# DroneSch.net
KiCad netlist of a schematic drawn in Altium Designer
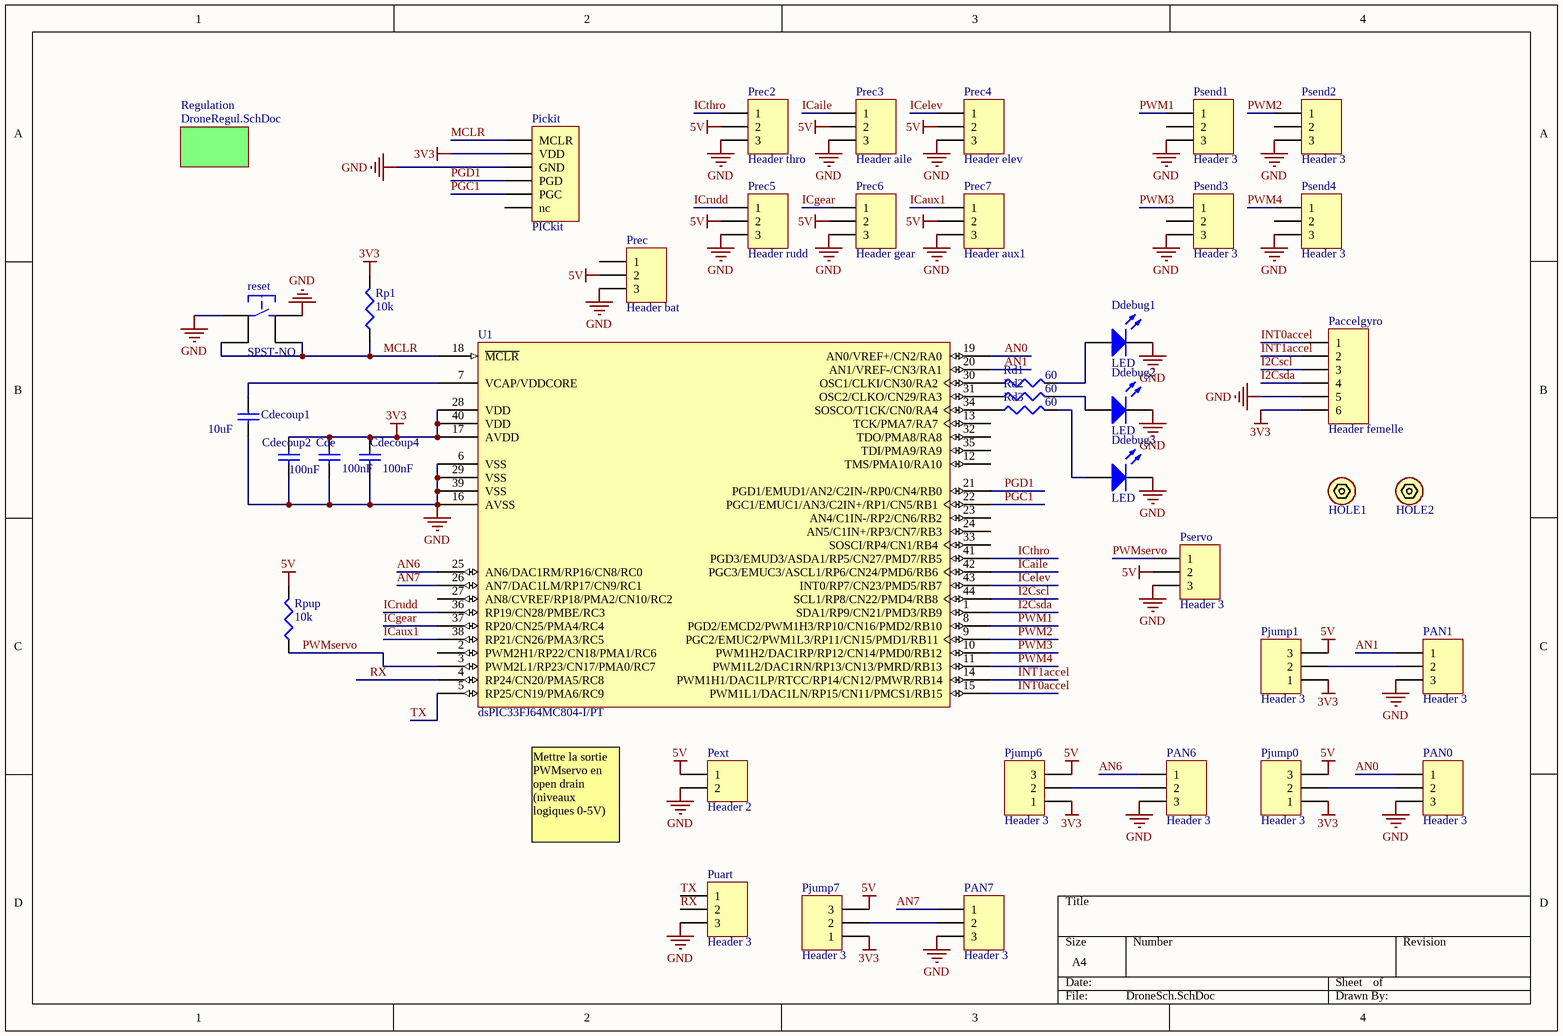
[diagram p0: DroneSch.SchDoc]

(export (version "E")
  (design (tool "Eeschema 10.0.6"))
  (components
    (comp (ref "Cde")
      (value "100nF")
      (footprint "C0805C")
      (description "Capacitor")
      (fields (field (name "Comment") "CAP") (field (name "PUBLISHER") "Altium Limited"))
      (libsource (lib "7Robot") (part "CAP"))
    )
    (comp (ref "Cdecoup1")
      (value "10uF")
      (footprint "C0805C")
      (description "Capacitor")
      (fields (field (name "Comment") "CAP") (field (name "PUBLISHER") "Altium Limited"))
      (libsource (lib "7Robot") (part "CAP"))
    )
    (comp (ref "Cdecoup2")
      (value "100nF")
      (footprint "C0805C")
      (description "Capacitor")
      (fields (field (name "Comment") "CAP") (field (name "PUBLISHER") "Altium Limited"))
      (libsource (lib "7Robot") (part "CAP"))
    )
    (comp (ref "Cdecoup4")
      (value "100nF")
      (footprint "C0805C")
      (description "Capacitor")
      (fields (field (name "Comment") "CAP") (field (name "PUBLISHER") "Altium Limited"))
      (libsource (lib "7Robot") (part "CAP"))
    )
    (comp (ref "Ddebug1")
      (value "LED")
      (footprint "LED1206R")
      (description "Typical LED")
      (fields (field (name "PUBLISHER") "Altium Limited"))
      (libsource (lib "7Robot") (part "LED"))
    )
    (comp (ref "Ddebug2")
      (value "LED")
      (footprint "LED1206Y")
      (description "Typical LED")
      (fields (field (name "PUBLISHER") "Altium Limited"))
      (libsource (lib "7Robot") (part "LED"))
    )
    (comp (ref "Ddebug3")
      (value "LED")
      (footprint "LED1206G")
      (description "Typical LED")
      (fields (field (name "PUBLISHER") "Altium Limited"))
      (libsource (lib "7Robot") (part "LED"))
    )
    (comp (ref "HOLE1")
      (value "Hole")
      (footprint "SCREW")
      (description "Mounting Hole for screws")
      (libsource (lib "7Robot") (part "Hole"))
    )
    (comp (ref "HOLE2")
      (value "Hole")
      (footprint "SCREW")
      (description "Mounting Hole for screws")
      (libsource (lib "7Robot") (part "Hole"))
    )
    (comp (ref "Paccelgyro")
      (value "Header femelle")
      (footprint "HDR1X6")
      (description "Header, 6-Pin")
      (fields (field (name "PUBLISHER") "Altium Limited"))
      (libsource (lib "7Robot") (part "Header 6"))
    )
    (comp (ref "PAN0")
      (value "Header 3")
      (footprint "HDR1X3")
      (description "Header, 3-Pin")
      (fields (field (name "PUBLISHER") "Altium Limited"))
      (libsource (lib "7Robot") (part "Header 3"))
    )
    (comp (ref "PAN1")
      (value "Header 3")
      (footprint "HDR1X3")
      (description "Header, 3-Pin")
      (fields (field (name "PUBLISHER") "Altium Limited"))
      (libsource (lib "7Robot") (part "Header 3"))
    )
    (comp (ref "PAN6")
      (value "Header 3")
      (footprint "HDR1X3")
      (description "Header, 3-Pin")
      (fields (field (name "PUBLISHER") "Altium Limited"))
      (libsource (lib "7Robot") (part "Header 3"))
    )
    (comp (ref "PAN7")
      (value "Header 3")
      (footprint "HDR1X3")
      (description "Header, 3-Pin")
      (fields (field (name "PUBLISHER") "Altium Limited"))
      (libsource (lib "7Robot") (part "Header 3"))
    )
    (comp (ref "Pext")
      (value "Header 2")
      (footprint "TERM2W-3.5")
      (description "Header, 2-Pin")
      (fields (field (name "PUBLISHER") "Altium Limited"))
      (libsource (lib "7Robot") (part "Header 2"))
    )
    (comp (ref "Pickit")
      (value "PICkit")
      (footprint "HDR1X6H")
      (description "Header, 6-Pin, Right Angle")
      (fields (field (name "PUBLISHER") "Altium Limited"))
      (libsource (lib "7Robot") (part "Header ICSP"))
    )
    (comp (ref "Pjump0")
      (value "Header 3")
      (footprint "HDR1X3")
      (description "Header, 3-Pin")
      (fields (field (name "PUBLISHER") "Altium Limited"))
      (libsource (lib "") (part "Header 3_1"))
    )
    (comp (ref "Pjump1")
      (value "Header 3")
      (footprint "HDR1X3")
      (description "Header, 3-Pin")
      (fields (field (name "PUBLISHER") "Altium Limited"))
      (libsource (lib "") (part "Header 3_1"))
    )
    (comp (ref "Pjump6")
      (value "Header 3")
      (footprint "HDR1X3")
      (description "Header, 3-Pin")
      (fields (field (name "PUBLISHER") "Altium Limited"))
      (libsource (lib "") (part "Header 3_1"))
    )
    (comp (ref "Pjump7")
      (value "Header 3")
      (footprint "HDR1X3")
      (description "Header, 3-Pin")
      (fields (field (name "PUBLISHER") "Altium Limited"))
      (libsource (lib "") (part "Header 3_1"))
    )
    (comp (ref "Prec")
      (value "Header bat")
      (footprint "HDR1X3")
      (description "Header, 3-Pin")
      (fields (field (name "PUBLISHER") "Altium Limited"))
      (libsource (lib "7Robot") (part "Header 3"))
    )
    (comp (ref "Prec2")
      (value "Header thro")
      (footprint "HDR1X3")
      (description "Header, 3-Pin")
      (fields (field (name "PUBLISHER") "Altium Limited"))
      (libsource (lib "7Robot") (part "Header 3"))
    )
    (comp (ref "Prec3")
      (value "Header aile")
      (footprint "HDR1X3")
      (description "Header, 3-Pin")
      (fields (field (name "PUBLISHER") "Altium Limited"))
      (libsource (lib "7Robot") (part "Header 3"))
    )
    (comp (ref "Prec4")
      (value "Header elev")
      (footprint "HDR1X3")
      (description "Header, 3-Pin")
      (fields (field (name "PUBLISHER") "Altium Limited"))
      (libsource (lib "7Robot") (part "Header 3"))
    )
    (comp (ref "Prec5")
      (value "Header rudd")
      (footprint "HDR1X3")
      (description "Header, 3-Pin")
      (fields (field (name "PUBLISHER") "Altium Limited"))
      (libsource (lib "7Robot") (part "Header 3"))
    )
    (comp (ref "Prec6")
      (value "Header gear")
      (footprint "HDR1X3")
      (description "Header, 3-Pin")
      (fields (field (name "PUBLISHER") "Altium Limited"))
      (libsource (lib "7Robot") (part "Header 3"))
    )
    (comp (ref "Prec7")
      (value "Header aux1")
      (footprint "HDR1X3")
      (description "Header, 3-Pin")
      (fields (field (name "PUBLISHER") "Altium Limited"))
      (libsource (lib "7Robot") (part "Header 3"))
    )
    (comp (ref "Psend1")
      (value "Header 3")
      (footprint "HDR1X3")
      (description "Header, 3-Pin")
      (fields (field (name "PUBLISHER") "Altium Limited"))
      (libsource (lib "7Robot") (part "Header 3"))
    )
    (comp (ref "Psend2")
      (value "Header 3")
      (footprint "HDR1X3")
      (description "Header, 3-Pin")
      (fields (field (name "PUBLISHER") "Altium Limited"))
      (libsource (lib "7Robot") (part "Header 3"))
    )
    (comp (ref "Psend3")
      (value "Header 3")
      (footprint "HDR1X3")
      (description "Header, 3-Pin")
      (fields (field (name "PUBLISHER") "Altium Limited"))
      (libsource (lib "7Robot") (part "Header 3"))
    )
    (comp (ref "Psend4")
      (value "Header 3")
      (footprint "HDR1X3")
      (description "Header, 3-Pin")
      (fields (field (name "PUBLISHER") "Altium Limited"))
      (libsource (lib "7Robot") (part "Header 3"))
    )
    (comp (ref "Pservo")
      (value "Header 3")
      (footprint "HDR1X3")
      (description "Header, 3-Pin")
      (fields (field (name "PUBLISHER") "Altium Limited"))
      (libsource (lib "7Robot") (part "Header 3"))
    )
    (comp (ref "Puart")
      (value "Header 3")
      (footprint "HDR1X3")
      (description "Header, 3-Pin")
      (fields (field (name "PUBLISHER") "Altium Limited"))
      (libsource (lib "7Robot") (part "Header 3"))
    )
    (comp (ref "Rd1")
      (value "60")
      (footprint "C0805R")
      (description "Resistor")
      (fields (field (name "Comment") "RES") (field (name "PUBLISHER") "Altium Limited"))
      (libsource (lib "7Robot") (part "RES"))
    )
    (comp (ref "Rd2")
      (value "60")
      (footprint "C0805R")
      (description "Resistor")
      (fields (field (name "Comment") "RES") (field (name "PUBLISHER") "Altium Limited"))
      (libsource (lib "7Robot") (part "RES"))
    )
    (comp (ref "Rd3")
      (value "60")
      (footprint "C0805R")
      (description "Resistor")
      (fields (field (name "Comment") "RES") (field (name "PUBLISHER") "Altium Limited"))
      (libsource (lib "7Robot") (part "RES"))
    )
    (comp (ref "reset")
      (value "SPST-NO")
      (footprint "SPST-NO")
      (description "Tactile Switch 7.3mm, SMD")
      (libsource (lib "7Robot") (part "SPST-NO"))
    )
    (comp (ref "Rp1")
      (value "10k")
      (footprint "C0805R")
      (description "Resistor")
      (fields (field (name "Comment") "RES") (field (name "PUBLISHER") "Altium Limited"))
      (libsource (lib "7Robot") (part "RES"))
    )
    (comp (ref "Rpup")
      (value "10k")
      (footprint "C0805R")
      (description "Resistor")
      (fields (field (name "Comment") "RES") (field (name "PUBLISHER") "Altium Limited"))
      (libsource (lib "7Robot") (part "RES"))
    )
    (comp (ref "U1")
      (value "dsPIC33FJ64MC804-I/PT")
      (footprint "TQFP-PT44_N")
      (fields (field (name "PUBLISHER") "Altium Limited"))
      (libsource (lib "7Robot") (part "dsPIC33FJ64MC804-I/PT"))
    )
  )
  (nets
    (net (code "1") (name "/AN0") (class "Default")
      (node (ref "PAN0") (pin "1") (pinfunction "1_1") (pintype "passive"))
      (node (ref "U1") (pin "19") (pinfunction "AN0/VREF+/CN2/RA0_19") (pintype "bidirectional"))
    )
    (net (code "2") (name "/AN1") (class "Default")
      (node (ref "PAN1") (pin "1") (pinfunction "1_1") (pintype "passive"))
      (node (ref "U1") (pin "20") (pinfunction "AN1/VREF-/CN3/RA1_20") (pintype "bidirectional"))
    )
    (net (code "3") (name "/AN6") (class "Default")
      (node (ref "PAN6") (pin "1") (pinfunction "1_1") (pintype "passive"))
      (node (ref "U1") (pin "25") (pinfunction "AN6/DAC1RM/RP16/CN8/RC0_25") (pintype "bidirectional"))
    )
    (net (code "4") (name "/AN7") (class "Default")
      (node (ref "PAN7") (pin "1") (pinfunction "1_1") (pintype "passive"))
      (node (ref "U1") (pin "26") (pinfunction "AN7/DAC1LM/RP17/CN9/RC1_26") (pintype "bidirectional"))
    )
    (net (code "5") (name "/I2Cscl") (class "Default")
      (node (ref "Paccelgyro") (pin "3") (pinfunction "3_3") (pintype "passive"))
      (node (ref "U1") (pin "44") (pinfunction "SCL1/RP8/CN22/PMD4/RB8_44") (pintype "bidirectional"))
    )
    (net (code "6") (name "/I2Csda") (class "Default")
      (node (ref "Paccelgyro") (pin "4") (pinfunction "4_4") (pintype "passive"))
      (node (ref "U1") (pin "1") (pinfunction "SDA1/RP9/CN21/PMD3/RB9_1") (pintype "bidirectional"))
    )
    (net (code "7") (name "/ICaile") (class "Default")
      (node (ref "Prec3") (pin "1") (pinfunction "1_1") (pintype "passive"))
      (node (ref "U1") (pin "42") (pinfunction "PGC3/EMUC3/ASCL1/RP6/CN24/PMD6/RB6_42") (pintype "bidirectional"))
    )
    (net (code "8") (name "/ICaux1") (class "Default")
      (node (ref "Prec7") (pin "1") (pinfunction "1_1") (pintype "passive"))
      (node (ref "U1") (pin "38") (pinfunction "RP21/CN26/PMA3/RC5_38") (pintype "bidirectional"))
    )
    (net (code "9") (name "/ICelev") (class "Default")
      (node (ref "Prec4") (pin "1") (pinfunction "1_1") (pintype "passive"))
      (node (ref "U1") (pin "43") (pinfunction "INT0/RP7/CN23/PMD5/RB7_43") (pintype "bidirectional"))
    )
    (net (code "10") (name "/ICgear") (class "Default")
      (node (ref "Prec6") (pin "1") (pinfunction "1_1") (pintype "passive"))
      (node (ref "U1") (pin "37") (pinfunction "RP20/CN25/PMA4/RC4_37") (pintype "bidirectional"))
    )
    (net (code "11") (name "/ICrudd") (class "Default")
      (node (ref "Prec5") (pin "1") (pinfunction "1_1") (pintype "passive"))
      (node (ref "U1") (pin "36") (pinfunction "RP19/CN28/PMBE/RC3_36") (pintype "bidirectional"))
    )
    (net (code "12") (name "/ICthro") (class "Default")
      (node (ref "Prec2") (pin "1") (pinfunction "1_1") (pintype "passive"))
      (node (ref "U1") (pin "41") (pinfunction "PGD3/EMUD3/ASDA1/RP5/CN27/PMD7/RB5_41") (pintype "bidirectional"))
    )
    (net (code "13") (name "/INT0accel") (class "Default")
      (node (ref "Paccelgyro") (pin "1") (pinfunction "1_1") (pintype "passive"))
      (node (ref "U1") (pin "15") (pinfunction "PWM1L1/DAC1LN/RP15/CN11/PMCS1/RB15_15") (pintype "bidirectional"))
    )
    (net (code "14") (name "/INT1accel") (class "Default")
      (node (ref "Paccelgyro") (pin "2") (pinfunction "2_2") (pintype "passive"))
      (node (ref "U1") (pin "14") (pinfunction "PWM1H1/DAC1LP/RTCC/RP14/CN12/PMWR/RB14_14") (pintype "bidirectional"))
    )
    (net (code "15") (name "/MCLR") (class "Default")
      (node (ref "Pickit") (pin "1") (pinfunction "MCLR_1") (pintype "passive"))
      (node (ref "Rp1") (pin "1") (pinfunction "1_1") (pintype "passive"))
      (node (ref "U1") (pin "18") (pinfunction "~{MCLR}_18") (pintype "input"))
      (node (ref "reset") (pin "2") (pintype "passive"))
      (node (ref "reset") (pin "3") (pintype "passive"))
    )
    (net (code "16") (name "/PGC1") (class "Default")
      (node (ref "Pickit") (pin "5") (pinfunction "PGC_5") (pintype "passive"))
      (node (ref "U1") (pin "22") (pinfunction "PGC1/EMUC1/AN3/C2IN+/RP1/CN5/RB1_22") (pintype "bidirectional"))
    )
    (net (code "17") (name "/PGD1") (class "Default")
      (node (ref "Pickit") (pin "4") (pinfunction "PGD_4") (pintype "passive"))
      (node (ref "U1") (pin "21") (pinfunction "PGD1/EMUD1/AN2/C2IN-/RP0/CN4/RB0_21") (pintype "bidirectional"))
    )
    (net (code "18") (name "/PWM1") (class "Default")
      (node (ref "Psend1") (pin "1") (pinfunction "1_1") (pintype "passive"))
      (node (ref "U1") (pin "8") (pinfunction "PGD2/EMCD2/PWM1H3/RP10/CN16/PMD2/RB10_8") (pintype "bidirectional"))
    )
    (net (code "19") (name "/PWM2") (class "Default")
      (node (ref "Psend2") (pin "1") (pinfunction "1_1") (pintype "passive"))
      (node (ref "U1") (pin "9") (pinfunction "PGC2/EMUC2/PWM1L3/RP11/CN15/PMD1/RB11_9") (pintype "bidirectional"))
    )
    (net (code "20") (name "/PWM3") (class "Default")
      (node (ref "Psend3") (pin "1") (pinfunction "1_1") (pintype "passive"))
      (node (ref "U1") (pin "10") (pinfunction "PWM1H2/DAC1RP/RP12/CN14/PMD0/RB12_10") (pintype "bidirectional"))
    )
    (net (code "21") (name "/PWM4") (class "Default")
      (node (ref "Psend4") (pin "1") (pinfunction "1_1") (pintype "passive"))
      (node (ref "U1") (pin "11") (pinfunction "PWM1L2/DAC1RN/RP13/CN13/PMRD/RB13_11") (pintype "bidirectional"))
    )
    (net (code "22") (name "/PWMservo") (class "Default")
      (node (ref "Pservo") (pin "1") (pinfunction "1_1") (pintype "passive"))
      (node (ref "Rpup") (pin "1") (pinfunction "1_1") (pintype "passive"))
      (node (ref "U1") (pin "3") (pinfunction "PWM2L1/RP23/CN17/PMA0/RC7_3") (pintype "bidirectional"))
    )
    (net (code "23") (name "/RX") (class "Default")
      (node (ref "Puart") (pin "2") (pinfunction "2_2") (pintype "passive"))
      (node (ref "U1") (pin "4") (pinfunction "RP24/CN20/PMA5/RC8_4") (pintype "bidirectional"))
    )
    (net (code "24") (name "/TX") (class "Default")
      (node (ref "Puart") (pin "1") (pinfunction "1_1") (pintype "passive"))
      (node (ref "U1") (pin "5") (pinfunction "RP25/CN19/PMA6/RC9_5") (pintype "bidirectional"))
    )
    (net (code "25") (name "3V3") (class "Default")
      (node (ref "Cde") (pin "2") (pinfunction "2_2") (pintype "passive"))
      (node (ref "Cdecoup2") (pin "2") (pinfunction "2_2") (pintype "passive"))
      (node (ref "Cdecoup4") (pin "2") (pinfunction "2_2") (pintype "passive"))
      (node (ref "Paccelgyro") (pin "6") (pinfunction "6_6") (pintype "passive"))
      (node (ref "Pickit") (pin "2") (pinfunction "VDD_2") (pintype "passive"))
      (node (ref "Pjump0") (pin "1") (pinfunction "1_1") (pintype "passive"))
      (node (ref "Pjump1") (pin "1") (pinfunction "1_1") (pintype "passive"))
      (node (ref "Pjump6") (pin "1") (pinfunction "1_1") (pintype "passive"))
      (node (ref "Pjump7") (pin "1") (pinfunction "1_1") (pintype "passive"))
      (node (ref "Rp1") (pin "2") (pinfunction "2_2") (pintype "passive"))
      (node (ref "U1") (pin "17") (pinfunction "AVDD_17") (pintype "power_in"))
      (node (ref "U1") (pin "28") (pinfunction "VDD_28") (pintype "power_in"))
      (node (ref "U1") (pin "40") (pinfunction "VDD_40") (pintype "power_in"))
    )
    (net (code "26") (name "5V") (class "Default")
      (node (ref "Pext") (pin "1") (pinfunction "1_1") (pintype "passive"))
      (node (ref "Pjump0") (pin "3") (pinfunction "3_3") (pintype "passive"))
      (node (ref "Pjump1") (pin "3") (pinfunction "3_3") (pintype "passive"))
      (node (ref "Pjump6") (pin "3") (pinfunction "3_3") (pintype "passive"))
      (node (ref "Pjump7") (pin "3") (pinfunction "3_3") (pintype "passive"))
      (node (ref "Prec") (pin "2") (pinfunction "2_2") (pintype "passive"))
      (node (ref "Prec2") (pin "2") (pinfunction "2_2") (pintype "passive"))
      (node (ref "Prec3") (pin "2") (pinfunction "2_2") (pintype "passive"))
      (node (ref "Prec4") (pin "2") (pinfunction "2_2") (pintype "passive"))
      (node (ref "Prec5") (pin "2") (pinfunction "2_2") (pintype "passive"))
      (node (ref "Prec6") (pin "2") (pinfunction "2_2") (pintype "passive"))
      (node (ref "Prec7") (pin "2") (pinfunction "2_2") (pintype "passive"))
      (node (ref "Pservo") (pin "2") (pinfunction "2_2") (pintype "passive"))
      (node (ref "Rpup") (pin "2") (pinfunction "2_2") (pintype "passive"))
    )
    (net (code "27") (name "GND") (class "Default")
      (node (ref "Cde") (pin "1") (pinfunction "1_1") (pintype "passive"))
      (node (ref "Cdecoup1") (pin "1") (pinfunction "1_1") (pintype "passive"))
      (node (ref "Cdecoup2") (pin "1") (pinfunction "1_1") (pintype "passive"))
      (node (ref "Cdecoup4") (pin "1") (pinfunction "1_1") (pintype "passive"))
      (node (ref "Ddebug1") (pin "2") (pinfunction "K_2") (pintype "passive"))
      (node (ref "Ddebug2") (pin "2") (pinfunction "K_2") (pintype "passive"))
      (node (ref "Ddebug3") (pin "2") (pinfunction "K_2") (pintype "passive"))
      (node (ref "PAN0") (pin "3") (pinfunction "3_3") (pintype "passive"))
      (node (ref "PAN1") (pin "3") (pinfunction "3_3") (pintype "passive"))
      (node (ref "PAN6") (pin "3") (pinfunction "3_3") (pintype "passive"))
      (node (ref "PAN7") (pin "3") (pinfunction "3_3") (pintype "passive"))
      (node (ref "Paccelgyro") (pin "5") (pinfunction "5_5") (pintype "passive"))
      (node (ref "Pext") (pin "2") (pinfunction "2_2") (pintype "passive"))
      (node (ref "Pickit") (pin "3") (pinfunction "GND_3") (pintype "passive"))
      (node (ref "Prec") (pin "3") (pinfunction "3_3") (pintype "passive"))
      (node (ref "Prec2") (pin "3") (pinfunction "3_3") (pintype "passive"))
      (node (ref "Prec3") (pin "3") (pinfunction "3_3") (pintype "passive"))
      (node (ref "Prec4") (pin "3") (pinfunction "3_3") (pintype "passive"))
      (node (ref "Prec5") (pin "3") (pinfunction "3_3") (pintype "passive"))
      (node (ref "Prec6") (pin "3") (pinfunction "3_3") (pintype "passive"))
      (node (ref "Prec7") (pin "3") (pinfunction "3_3") (pintype "passive"))
      (node (ref "Psend1") (pin "3") (pinfunction "3_3") (pintype "passive"))
      (node (ref "Psend2") (pin "3") (pinfunction "3_3") (pintype "passive"))
      (node (ref "Psend3") (pin "3") (pinfunction "3_3") (pintype "passive"))
      (node (ref "Psend4") (pin "3") (pinfunction "3_3") (pintype "passive"))
      (node (ref "Pservo") (pin "3") (pinfunction "3_3") (pintype "passive"))
      (node (ref "Puart") (pin "3") (pinfunction "3_3") (pintype "passive"))
      (node (ref "U1") (pin "16") (pinfunction "AVSS_16") (pintype "power_in"))
      (node (ref "U1") (pin "29") (pinfunction "VSS_29") (pintype "power_in"))
      (node (ref "U1") (pin "39") (pinfunction "VSS_39") (pintype "power_in"))
      (node (ref "U1") (pin "6") (pinfunction "VSS_6") (pintype "power_in"))
      (node (ref "reset") (pin "1") (pintype "passive"))
      (node (ref "reset") (pin "4") (pintype "passive"))
    )
    (net (code "28") (name "Net-(Ddebug1-A)") (class "Default")
      (node (ref "Ddebug1") (pin "1") (pinfunction "A_1") (pintype "passive"))
      (node (ref "Rd1") (pin "2") (pinfunction "2_2") (pintype "passive"))
    )
    (net (code "29") (name "Net-(Ddebug2-A)") (class "Default")
      (node (ref "Ddebug2") (pin "1") (pinfunction "A_1") (pintype "passive"))
      (node (ref "Rd2") (pin "2") (pinfunction "2_2") (pintype "passive"))
    )
    (net (code "30") (name "Net-(Ddebug3-A)") (class "Default")
      (node (ref "Ddebug3") (pin "1") (pinfunction "A_1") (pintype "passive"))
      (node (ref "Rd3") (pin "2") (pinfunction "2_2") (pintype "passive"))
    )
    (net (code "31") (name "Net-(PAN0-Pad2)") (class "Default")
      (node (ref "PAN0") (pin "2") (pinfunction "2_2") (pintype "passive"))
      (node (ref "Pjump0") (pin "2") (pinfunction "2_2") (pintype "passive"))
    )
    (net (code "32") (name "Net-(PAN1-Pad2)") (class "Default")
      (node (ref "PAN1") (pin "2") (pinfunction "2_2") (pintype "passive"))
      (node (ref "Pjump1") (pin "2") (pinfunction "2_2") (pintype "passive"))
    )
    (net (code "33") (name "Net-(PAN6-Pad2)") (class "Default")
      (node (ref "PAN6") (pin "2") (pinfunction "2_2") (pintype "passive"))
      (node (ref "Pjump6") (pin "2") (pinfunction "2_2") (pintype "passive"))
    )
    (net (code "34") (name "Net-(PAN7-Pad2)") (class "Default")
      (node (ref "PAN7") (pin "2") (pinfunction "2_2") (pintype "passive"))
      (node (ref "Pjump7") (pin "2") (pinfunction "2_2") (pintype "passive"))
    )
    (net (code "35") (name "Net-(U1-OSC1{slash}CLKI{slash}CN30{slash}RA2)") (class "Default")
      (node (ref "Rd1") (pin "1") (pinfunction "1_1") (pintype "passive"))
      (node (ref "U1") (pin "30") (pinfunction "OSC1/CLKI/CN30/RA2_30") (pintype "bidirectional"))
    )
    (net (code "36") (name "Net-(U1-OSC2{slash}CLKO{slash}CN29{slash}RA3)") (class "Default")
      (node (ref "Rd2") (pin "1") (pinfunction "1_1") (pintype "passive"))
      (node (ref "U1") (pin "31") (pinfunction "OSC2/CLKO/CN29/RA3_31") (pintype "bidirectional"))
    )
    (net (code "37") (name "Net-(U1-SOSCO{slash}T1CK{slash}CN0{slash}RA4)") (class "Default")
      (node (ref "Rd3") (pin "1") (pinfunction "1_1") (pintype "passive"))
      (node (ref "U1") (pin "34") (pinfunction "SOSCO/T1CK/CN0/RA4_34") (pintype "bidirectional"))
    )
    (net (code "38") (name "Net-(U1-VCAP{slash}VDDCORE)") (class "Default")
      (node (ref "Cdecoup1") (pin "2") (pinfunction "2_2") (pintype "passive"))
      (node (ref "U1") (pin "7") (pinfunction "VCAP/VDDCORE_7") (pintype "power_in"))
    )
    (net (code "39") (name "unconnected-(HOLE1-Hole-Pad1)") (class "Default")
      (node (ref "HOLE1") (pin "1") (pinfunction "Hole_1") (pintype "passive"))
    )
    (net (code "40") (name "unconnected-(HOLE2-Hole-Pad1)") (class "Default")
      (node (ref "HOLE2") (pin "1") (pinfunction "Hole_1") (pintype "passive"))
    )
    (net (code "41") (name "unconnected-(Pickit-nc-Pad6)") (class "Default")
      (node (ref "Pickit") (pin "6") (pinfunction "nc_6") (pintype "passive"))
    )
    (net (code "42") (name "unconnected-(Prec-Pad1)") (class "Default")
      (node (ref "Prec") (pin "1") (pinfunction "1_1") (pintype "passive"))
    )
    (net (code "43") (name "unconnected-(Psend1-Pad2)") (class "Default")
      (node (ref "Psend1") (pin "2") (pinfunction "2_2") (pintype "passive"))
    )
    (net (code "44") (name "unconnected-(Psend2-Pad2)") (class "Default")
      (node (ref "Psend2") (pin "2") (pinfunction "2_2") (pintype "passive"))
    )
    (net (code "45") (name "unconnected-(Psend3-Pad2)") (class "Default")
      (node (ref "Psend3") (pin "2") (pinfunction "2_2") (pintype "passive"))
    )
    (net (code "46") (name "unconnected-(Psend4-Pad2)") (class "Default")
      (node (ref "Psend4") (pin "2") (pinfunction "2_2") (pintype "passive"))
    )
    (net (code "47") (name "unconnected-(U1-AN4{slash}C1IN-{slash}RP2{slash}CN6{slash}RB2-Pad23)") (class "Default")
      (node (ref "U1") (pin "23") (pinfunction "AN4/C1IN-/RP2/CN6/RB2_23") (pintype "bidirectional"))
    )
    (net (code "48") (name "unconnected-(U1-AN5{slash}C1IN+{slash}RP3{slash}CN7{slash}RB3-Pad24)") (class "Default")
      (node (ref "U1") (pin "24") (pinfunction "AN5/C1IN+/RP3/CN7/RB3_24") (pintype "bidirectional"))
    )
    (net (code "49") (name "unconnected-(U1-AN8{slash}CVREF{slash}RP18{slash}PMA2{slash}CN10{slash}RC2-Pad27)") (class "Default")
      (node (ref "U1") (pin "27") (pinfunction "AN8/CVREF/RP18/PMA2/CN10/RC2_27") (pintype "bidirectional"))
    )
    (net (code "50") (name "unconnected-(U1-PWM2H1{slash}RP22{slash}CN18{slash}PMA1{slash}RC6-Pad2)") (class "Default")
      (node (ref "U1") (pin "2") (pinfunction "PWM2H1/RP22/CN18/PMA1/RC6_2") (pintype "bidirectional"))
    )
    (net (code "51") (name "unconnected-(U1-SOSCI{slash}RP4{slash}CN1{slash}RB4-Pad33)") (class "Default")
      (node (ref "U1") (pin "33") (pinfunction "SOSCI/RP4/CN1/RB4_33") (pintype "bidirectional"))
    )
    (net (code "52") (name "unconnected-(U1-TCK{slash}PMA7{slash}RA7-Pad13)") (class "Default")
      (node (ref "U1") (pin "13") (pinfunction "TCK/PMA7/RA7_13") (pintype "bidirectional"))
    )
    (net (code "53") (name "unconnected-(U1-TDI{slash}PMA9{slash}RA9-Pad35)") (class "Default")
      (node (ref "U1") (pin "35") (pinfunction "TDI/PMA9/RA9_35") (pintype "bidirectional"))
    )
    (net (code "54") (name "unconnected-(U1-TDO{slash}PMA8{slash}RA8-Pad32)") (class "Default")
      (node (ref "U1") (pin "32") (pinfunction "TDO/PMA8/RA8_32") (pintype "bidirectional"))
    )
    (net (code "55") (name "unconnected-(U1-TMS{slash}PMA10{slash}RA10-Pad12)") (class "Default")
      (node (ref "U1") (pin "12") (pinfunction "TMS/PMA10/RA10_12") (pintype "bidirectional"))
    )
  )
)
